# CG65_Schematics.net
KiCad netlist of a schematic drawn in Altium Designer
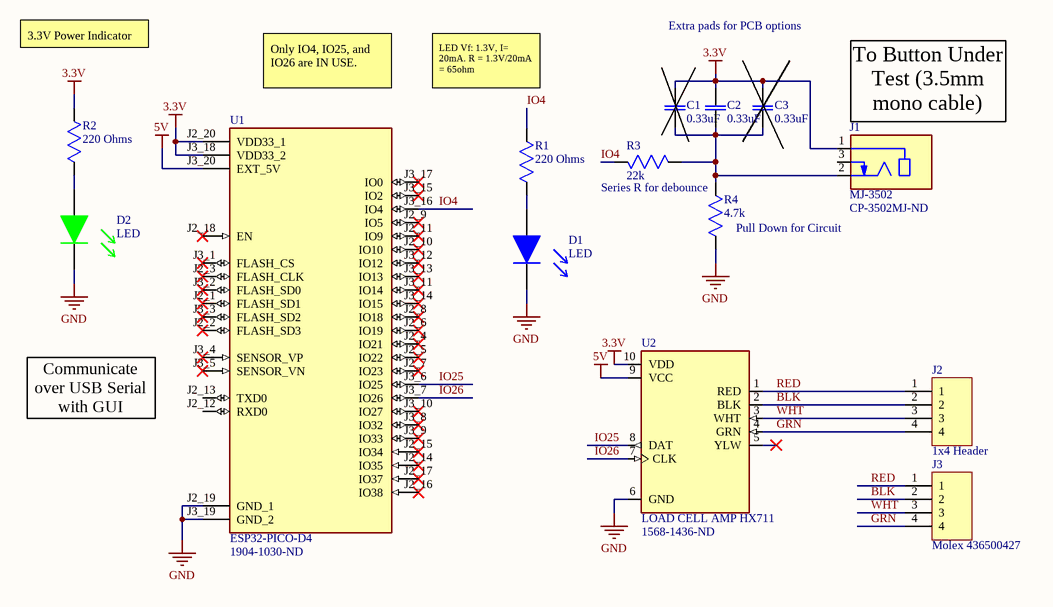
[diagram p0: CG65_Schematics.SchDoc]

(export (version "E")
  (design (tool "Eeschema 10.0.6"))
  (components
    (comp (ref "C1")
      (value "0.33uF")
      (footprint "TH CAPACITOR")
      (description "Standard Capacitor, Through Hole")
      (libsource (lib "SchematicLibrary") (part "Capacitor"))
    )
    (comp (ref "C2")
      (value "0.33uF")
      (footprint "TH CAPACITOR")
      (description "Standard Capacitor, Through Hole")
      (libsource (lib "SchematicLibrary") (part "Capacitor"))
    )
    (comp (ref "C3")
      (value "0.33uF")
      (footprint "TH CAPACITOR")
      (description "Standard Capacitor, Through Hole")
      (libsource (lib "SchematicLibrary") (part "Capacitor"))
    )
    (comp (ref "D1")
      (value "LED")
      (footprint "LED TH")
      (description "2V Blue LED Through Hole")
      (libsource (lib "SchematicLibrary") (part "LED Blue"))
    )
    (comp (ref "D2")
      (value "LED")
      (footprint "LED TH")
      (description "2V Green LED Through Hole")
      (libsource (lib "SchematicLibrary") (part "LED Green"))
    )
    (comp (ref "J1")
      (value "MJ-3502")
      (footprint "MJ-3502N")
      (description "3.5 mm, Mono, Right Angle, Through Hole, Threaded Bushing, Audio Jack Connector")
      (fields (field (name "MANUFACTURER") "CUI") (field (name "SUPPLIER PART NUMBER 1") "CP-3502MJ-ND"))
      (libsource (lib "SchematicLibrary") (part "MJ-3502"))
    )
    (comp (ref "J2")
      (value "1x4 Header")
      (footprint "1x4 Standard Header")
      (description "Standard 0.1\" Header 1x4")
      (libsource (lib "SchematicLibrary") (part "1x4 Header"))
    )
    (comp (ref "J3")
      (value "Molex 436500427")
      (footprint "MOLEX_436500427")
      (description "Molex MicroFit 3.0 Header 1x4, mates with 0436450400")
      (libsource (lib "SchematicLibrary") (part "Molex 436500427"))
    )
    (comp (ref "R1")
      (value "220 Ohms")
      (footprint "TH Resistor")
      (description "Standard Resistor, Through Hole, 1/8W")
      (libsource (lib "SchematicLibrary") (part "Resistor"))
    )
    (comp (ref "R2")
      (value "220 Ohms")
      (footprint "TH Resistor")
      (description "Standard Resistor, Through Hole, 1/8W")
      (libsource (lib "SchematicLibrary") (part "Resistor"))
    )
    (comp (ref "R3")
      (value "22k")
      (footprint "TH Resistor")
      (description "Standard Resistor, Through Hole, 1/8W")
      (libsource (lib "SchematicLibrary") (part "Resistor"))
    )
    (comp (ref "R4")
      (value "4.7k")
      (footprint "TH Resistor")
      (description "Standard Resistor, Through Hole, 1/8W")
      (libsource (lib "SchematicLibrary") (part "Resistor"))
    )
    (comp (ref "U1")
      (value "ESP32-PICO-D4")
      (footprint "ESP32-PICO-KIT")
      (description "ESP32 Wifi Bluetooth Eval Board")
      (fields
        (field (name "MANUFACTURER") "Espressif Systems")
        (field (name "MANUFACTURER PART NUMBER") "ESP32-PICO-KIT")
        (field (name "SUPPLIER PART NUMBER 1") "1904-1030-ND")
      )
      (libsource (lib "SchematicLibrary") (part "ESP32-PICO-KIT"))
    )
    (comp (ref "U2")
      (value "LOAD CELL AMP HX711")
      (footprint "SEN-13879")
      (description "HX711 Load Cell Amplifier")
      (fields
        (field (name "MANUFACTURER") "SparkFun")
        (field (name "MANUFACTURER PART NUMBER") "SEN-13879")
        (field (name "SUPPLIER PART NUMBER 1") "1568-1436-ND")
      )
      (libsource (lib "SchematicLibrary") (part "LOAD CELL AMP HX711"))
    )
  )
  (nets
    (net (code "1") (name "/BLK") (class "Default")
      (node (ref "J2") (pin "2") (pinfunction "2_2") (pintype "passive"))
      (node (ref "J3") (pin "2") (pinfunction "2_2") (pintype "passive"))
      (node (ref "U2") (pin "2") (pinfunction "BLK_2") (pintype "bidirectional"))
    )
    (net (code "2") (name "/GRN") (class "Default")
      (node (ref "J2") (pin "4") (pinfunction "4_4") (pintype "passive"))
      (node (ref "J3") (pin "4") (pinfunction "4_4") (pintype "passive"))
      (node (ref "U2") (pin "4") (pinfunction "GRN_4") (pintype "input"))
    )
    (net (code "3") (name "/IO4") (class "Default")
      (node (ref "R1") (pin "2") (pinfunction "R2_2") (pintype "passive"))
      (node (ref "R3") (pin "2") (pinfunction "R2_2") (pintype "passive"))
      (node (ref "U1") (pin "J3_16") (pinfunction "IO4_J3_16") (pintype "bidirectional"))
    )
    (net (code "4") (name "/IO25") (class "Default")
      (node (ref "U1") (pin "J3_6") (pinfunction "IO25_J3_6") (pintype "bidirectional"))
      (node (ref "U2") (pin "8") (pinfunction "DAT_8") (pintype "output"))
    )
    (net (code "5") (name "/IO26") (class "Default")
      (node (ref "U1") (pin "J3_7") (pinfunction "IO26_J3_7") (pintype "bidirectional"))
      (node (ref "U2") (pin "7") (pinfunction "CLK_7") (pintype "input"))
    )
    (net (code "6") (name "/RED") (class "Default")
      (node (ref "J2") (pin "1") (pinfunction "1_1") (pintype "passive"))
      (node (ref "J3") (pin "1") (pinfunction "1_1") (pintype "passive"))
      (node (ref "U2") (pin "1") (pinfunction "RED_1") (pintype "bidirectional"))
    )
    (net (code "7") (name "/WHT") (class "Default")
      (node (ref "J2") (pin "3") (pinfunction "3_3") (pintype "passive"))
      (node (ref "J3") (pin "3") (pinfunction "3_3") (pintype "passive"))
      (node (ref "U2") (pin "3") (pinfunction "WHT_3") (pintype "input"))
    )
    (net (code "8") (name "3.3V") (class "Default")
      (node (ref "C1") (pin "2") (pinfunction "2_2") (pintype "passive"))
      (node (ref "C2") (pin "2") (pinfunction "2_2") (pintype "passive"))
      (node (ref "C3") (pin "2") (pinfunction "2_2") (pintype "passive"))
      (node (ref "J1") (pin "1") (pinfunction "1_1") (pintype "passive"))
      (node (ref "R2") (pin "2") (pinfunction "R2_2") (pintype "passive"))
      (node (ref "U1") (pin "J2_20") (pinfunction "VDD33_1_J2_20") (pintype "power_in"))
      (node (ref "U1") (pin "J3_18") (pinfunction "VDD33_2_J3_18") (pintype "power_in"))
      (node (ref "U2") (pin "10") (pinfunction "VDD_10") (pintype "power_in"))
    )
    (net (code "9") (name "5V") (class "Default")
      (node (ref "U1") (pin "J3_20") (pinfunction "EXT_5V_J3_20") (pintype "power_in"))
      (node (ref "U2") (pin "9") (pinfunction "VCC_9") (pintype "power_in"))
    )
    (net (code "10") (name "GND") (class "Default")
      (node (ref "D1") (pin "1") (pinfunction "1_1") (pintype "passive"))
      (node (ref "D2") (pin "1") (pinfunction "1_1") (pintype "passive"))
      (node (ref "R4") (pin "1") (pinfunction "R1_1") (pintype "passive"))
      (node (ref "U1") (pin "J2_19") (pinfunction "GND_1_J2_19") (pintype "power_in"))
      (node (ref "U1") (pin "J3_19") (pinfunction "GND_2_J3_19") (pintype "power_in"))
      (node (ref "U2") (pin "6") (pinfunction "GND_6") (pintype "power_in"))
    )
    (net (code "11") (name "Net-(R1-R1)") (class "Default")
      (node (ref "D1") (pin "2") (pinfunction "2_2") (pintype "passive"))
      (node (ref "R1") (pin "1") (pinfunction "R1_1") (pintype "passive"))
    )
    (net (code "12") (name "Net-(R2-R1)") (class "Default")
      (node (ref "D2") (pin "2") (pinfunction "2_2") (pintype "passive"))
      (node (ref "R2") (pin "1") (pinfunction "R1_1") (pintype "passive"))
    )
    (net (code "13") (name "Net-(R3-R1)") (class "Default")
      (node (ref "C1") (pin "1") (pinfunction "1_1") (pintype "passive"))
      (node (ref "C2") (pin "1") (pinfunction "1_1") (pintype "passive"))
      (node (ref "C3") (pin "1") (pinfunction "1_1") (pintype "passive"))
      (node (ref "J1") (pin "2") (pinfunction "2_2") (pintype "passive"))
      (node (ref "R3") (pin "1") (pinfunction "R1_1") (pintype "passive"))
      (node (ref "R4") (pin "2") (pinfunction "R2_2") (pintype "passive"))
    )
    (net (code "14") (name "unconnected-(J1-Pad3)") (class "Default")
      (node (ref "J1") (pin "3") (pinfunction "3_3") (pintype "passive"))
    )
    (net (code "15") (name "unconnected-(U1-EN-PadJ2_18)") (class "Default")
      (node (ref "U1") (pin "J2_18") (pinfunction "EN_J2_18") (pintype "input+no_connect"))
    )
    (net (code "16") (name "unconnected-(U1-FLASH_CLK-PadJ2_3)") (class "Default")
      (node (ref "U1") (pin "J2_3") (pinfunction "FLASH_CLK_J2_3") (pintype "bidirectional+no_connect"))
    )
    (net (code "17") (name "unconnected-(U1-FLASH_CS-PadJ3_1)") (class "Default")
      (node (ref "U1") (pin "J3_1") (pinfunction "FLASH_CS_J3_1") (pintype "bidirectional+no_connect"))
    )
    (net (code "18") (name "unconnected-(U1-FLASH_SD0-PadJ3_2)") (class "Default")
      (node (ref "U1") (pin "J3_2") (pinfunction "FLASH_SD0_J3_2") (pintype "bidirectional+no_connect"))
    )
    (net (code "19") (name "unconnected-(U1-FLASH_SD1-PadJ2_1)") (class "Default")
      (node (ref "U1") (pin "J2_1") (pinfunction "FLASH_SD1_J2_1") (pintype "bidirectional+no_connect"))
    )
    (net (code "20") (name "unconnected-(U1-FLASH_SD2-PadJ3_3)") (class "Default")
      (node (ref "U1") (pin "J3_3") (pinfunction "FLASH_SD2_J3_3") (pintype "bidirectional+no_connect"))
    )
    (net (code "21") (name "unconnected-(U1-FLASH_SD3-PadJ2_2)") (class "Default")
      (node (ref "U1") (pin "J2_2") (pinfunction "FLASH_SD3_J2_2") (pintype "bidirectional+no_connect"))
    )
    (net (code "22") (name "unconnected-(U1-IO0-PadJ3_17)") (class "Default")
      (node (ref "U1") (pin "J3_17") (pinfunction "IO0_J3_17") (pintype "bidirectional+no_connect"))
    )
    (net (code "23") (name "unconnected-(U1-IO2-PadJ3_15)") (class "Default")
      (node (ref "U1") (pin "J3_15") (pinfunction "IO2_J3_15") (pintype "bidirectional+no_connect"))
    )
    (net (code "24") (name "unconnected-(U1-IO5-PadJ2_9)") (class "Default")
      (node (ref "U1") (pin "J2_9") (pinfunction "IO5_J2_9") (pintype "bidirectional+no_connect"))
    )
    (net (code "25") (name "unconnected-(U1-IO9-PadJ2_11)") (class "Default")
      (node (ref "U1") (pin "J2_11") (pinfunction "IO9_J2_11") (pintype "bidirectional+no_connect"))
    )
    (net (code "26") (name "unconnected-(U1-IO10-PadJ2_10)") (class "Default")
      (node (ref "U1") (pin "J2_10") (pinfunction "IO10_J2_10") (pintype "bidirectional+no_connect"))
    )
    (net (code "27") (name "unconnected-(U1-IO12-PadJ3_12)") (class "Default")
      (node (ref "U1") (pin "J3_12") (pinfunction "IO12_J3_12") (pintype "bidirectional+no_connect"))
    )
    (net (code "28") (name "unconnected-(U1-IO13-PadJ3_13)") (class "Default")
      (node (ref "U1") (pin "J3_13") (pinfunction "IO13_J3_13") (pintype "bidirectional+no_connect"))
    )
    (net (code "29") (name "unconnected-(U1-IO14-PadJ3_11)") (class "Default")
      (node (ref "U1") (pin "J3_11") (pinfunction "IO14_J3_11") (pintype "bidirectional+no_connect"))
    )
    (net (code "30") (name "unconnected-(U1-IO15-PadJ3_14)") (class "Default")
      (node (ref "U1") (pin "J3_14") (pinfunction "IO15_J3_14") (pintype "bidirectional+no_connect"))
    )
    (net (code "31") (name "unconnected-(U1-IO18-PadJ2_8)") (class "Default")
      (node (ref "U1") (pin "J2_8") (pinfunction "IO18_J2_8") (pintype "bidirectional+no_connect"))
    )
    (net (code "32") (name "unconnected-(U1-IO19-PadJ2_6)") (class "Default")
      (node (ref "U1") (pin "J2_6") (pinfunction "IO19_J2_6") (pintype "bidirectional+no_connect"))
    )
    (net (code "33") (name "unconnected-(U1-IO21-PadJ2_4)") (class "Default")
      (node (ref "U1") (pin "J2_4") (pinfunction "IO21_J2_4") (pintype "bidirectional+no_connect"))
    )
    (net (code "34") (name "unconnected-(U1-IO22-PadJ2_5)") (class "Default")
      (node (ref "U1") (pin "J2_5") (pinfunction "IO22_J2_5") (pintype "bidirectional+no_connect"))
    )
    (net (code "35") (name "unconnected-(U1-IO23-PadJ2_7)") (class "Default")
      (node (ref "U1") (pin "J2_7") (pinfunction "IO23_J2_7") (pintype "bidirectional+no_connect"))
    )
    (net (code "36") (name "unconnected-(U1-IO27-PadJ3_10)") (class "Default")
      (node (ref "U1") (pin "J3_10") (pinfunction "IO27_J3_10") (pintype "bidirectional+no_connect"))
    )
    (net (code "37") (name "unconnected-(U1-IO32-PadJ3_8)") (class "Default")
      (node (ref "U1") (pin "J3_8") (pinfunction "IO32_J3_8") (pintype "bidirectional+no_connect"))
    )
    (net (code "38") (name "unconnected-(U1-IO33-PadJ3_9)") (class "Default")
      (node (ref "U1") (pin "J3_9") (pinfunction "IO33_J3_9") (pintype "bidirectional+no_connect"))
    )
    (net (code "39") (name "unconnected-(U1-IO34-PadJ2_15)") (class "Default")
      (node (ref "U1") (pin "J2_15") (pinfunction "IO34_J2_15") (pintype "input+no_connect"))
    )
    (net (code "40") (name "unconnected-(U1-IO35-PadJ2_14)") (class "Default")
      (node (ref "U1") (pin "J2_14") (pinfunction "IO35_J2_14") (pintype "input+no_connect"))
    )
    (net (code "41") (name "unconnected-(U1-IO37-PadJ2_17)") (class "Default")
      (node (ref "U1") (pin "J2_17") (pinfunction "IO37_J2_17") (pintype "input+no_connect"))
    )
    (net (code "42") (name "unconnected-(U1-IO38-PadJ2_16)") (class "Default")
      (node (ref "U1") (pin "J2_16") (pinfunction "IO38_J2_16") (pintype "input+no_connect"))
    )
    (net (code "43") (name "unconnected-(U1-RXD0-PadJ2_12)") (class "Default")
      (node (ref "U1") (pin "J2_12") (pinfunction "RXD0_J2_12") (pintype "bidirectional"))
    )
    (net (code "44") (name "unconnected-(U1-SENSOR_VN-PadJ3_5)") (class "Default")
      (node (ref "U1") (pin "J3_5") (pinfunction "SENSOR_VN_J3_5") (pintype "input+no_connect"))
    )
    (net (code "45") (name "unconnected-(U1-SENSOR_VP-PadJ3_4)") (class "Default")
      (node (ref "U1") (pin "J3_4") (pinfunction "SENSOR_VP_J3_4") (pintype "input+no_connect"))
    )
    (net (code "46") (name "unconnected-(U1-TXD0-PadJ2_13)") (class "Default")
      (node (ref "U1") (pin "J2_13") (pinfunction "TXD0_J2_13") (pintype "bidirectional"))
    )
    (net (code "47") (name "unconnected-(U2-YLW-Pad5)") (class "Default")
      (node (ref "U2") (pin "5") (pinfunction "YLW_5") (pintype "bidirectional+no_connect"))
    )
  )
)
